# STM32H7_POWER_MISCELLANEOUS.net
KiCad netlist of a schematic drawn in Altium Designer
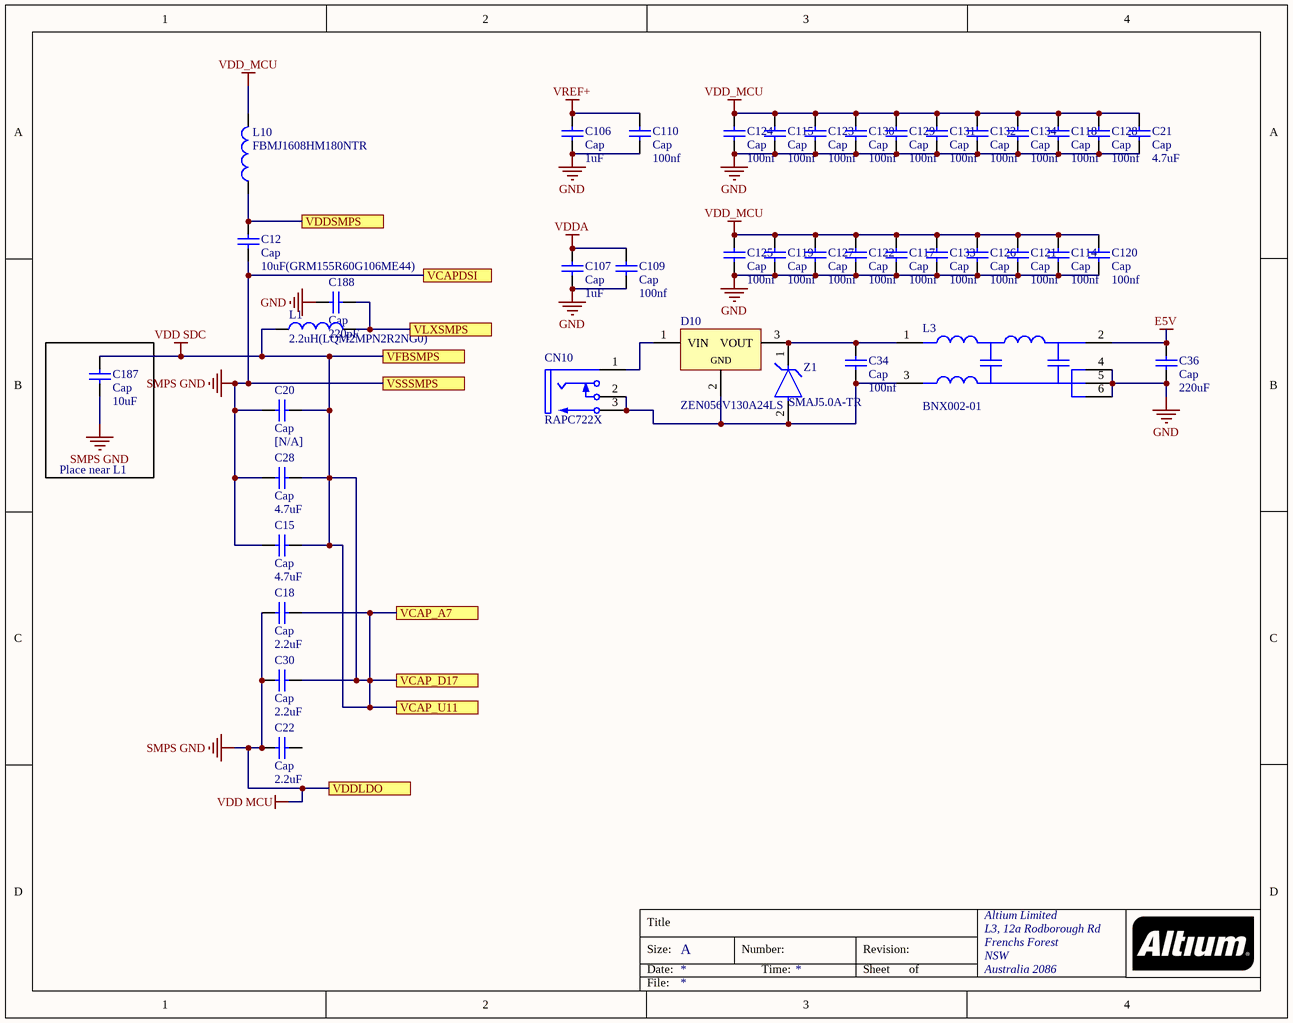
[diagram p0: STM32H7_POWER_MISCELLANEOUS.SchDoc]

(export (version "E")
  (design (tool "Eeschema 10.0.6"))
  (components
    (comp (ref "C12")
      (value "Cap")
      (footprint "RAD-0.3")
      (description "Capacitor")
      (fields
        (field (name "ALTIUM_VALUE") "10uF(GRM155R60G106ME44)")
        (field (name "PUBLISHER") "Altium Limited")
      )
      (libsource (lib "Miscellaneous Devices") (part "Cap"))
    )
    (comp (ref "C15")
      (value "Cap")
      (footprint "RAD-0.3")
      (description "Capacitor")
      (fields (field (name "ALTIUM_VALUE") "4.7uF") (field (name "PUBLISHER") "Altium Limited"))
      (libsource (lib "Miscellaneous Devices") (part "Cap"))
    )
    (comp (ref "C18")
      (value "Cap")
      (footprint "RAD-0.3")
      (description "Capacitor")
      (fields (field (name "ALTIUM_VALUE") "2.2uF") (field (name "PUBLISHER") "Altium Limited"))
      (libsource (lib "Miscellaneous Devices") (part "Cap"))
    )
    (comp (ref "C20")
      (value "Cap")
      (footprint "RAD-0.3")
      (description "Capacitor")
      (fields (field (name "ALTIUM_VALUE") "[N/A]") (field (name "PUBLISHER") "Altium Limited"))
      (libsource (lib "Miscellaneous Devices") (part "Cap"))
    )
    (comp (ref "C21")
      (value "Cap")
      (footprint "RAD-0.3")
      (description "Capacitor")
      (fields (field (name "ALTIUM_VALUE") "4.7uF") (field (name "PUBLISHER") "Altium Limited"))
      (libsource (lib "Miscellaneous Devices") (part "Cap"))
    )
    (comp (ref "C22")
      (value "Cap")
      (footprint "RAD-0.3")
      (description "Capacitor")
      (fields (field (name "ALTIUM_VALUE") "2.2uF") (field (name "PUBLISHER") "Altium Limited"))
      (libsource (lib "Miscellaneous Devices") (part "Cap"))
    )
    (comp (ref "C28")
      (value "Cap")
      (footprint "RAD-0.3")
      (description "Capacitor")
      (fields (field (name "ALTIUM_VALUE") "4.7uF") (field (name "PUBLISHER") "Altium Limited"))
      (libsource (lib "Miscellaneous Devices") (part "Cap"))
    )
    (comp (ref "C30")
      (value "Cap")
      (footprint "RAD-0.3")
      (description "Capacitor")
      (fields (field (name "ALTIUM_VALUE") "2.2uF") (field (name "PUBLISHER") "Altium Limited"))
      (libsource (lib "Miscellaneous Devices") (part "Cap"))
    )
    (comp (ref "C34")
      (value "Cap")
      (footprint "RAD-0.3")
      (description "Capacitor")
      (fields (field (name "ALTIUM_VALUE") "100nf") (field (name "PUBLISHER") "Altium Limited"))
      (libsource (lib "Miscellaneous Devices") (part "Cap"))
    )
    (comp (ref "C36")
      (value "Cap")
      (footprint "RAD-0.3")
      (description "Capacitor")
      (fields (field (name "ALTIUM_VALUE") "220uF") (field (name "PUBLISHER") "Altium Limited"))
      (libsource (lib "Miscellaneous Devices") (part "Cap"))
    )
    (comp (ref "C106")
      (value "Cap")
      (footprint "RAD-0.3")
      (description "Capacitor")
      (fields (field (name "ALTIUM_VALUE") "1uF") (field (name "PUBLISHER") "Altium Limited"))
      (libsource (lib "Miscellaneous Devices") (part "Cap"))
    )
    (comp (ref "C107")
      (value "Cap")
      (footprint "RAD-0.3")
      (description "Capacitor")
      (fields (field (name "ALTIUM_VALUE") "1uF") (field (name "PUBLISHER") "Altium Limited"))
      (libsource (lib "Miscellaneous Devices") (part "Cap"))
    )
    (comp (ref "C109")
      (value "Cap")
      (footprint "RAD-0.3")
      (description "Capacitor")
      (fields (field (name "ALTIUM_VALUE") "100nf") (field (name "PUBLISHER") "Altium Limited"))
      (libsource (lib "Miscellaneous Devices") (part "Cap"))
    )
    (comp (ref "C110")
      (value "Cap")
      (footprint "RAD-0.3")
      (description "Capacitor")
      (fields (field (name "ALTIUM_VALUE") "100nf") (field (name "PUBLISHER") "Altium Limited"))
      (libsource (lib "Miscellaneous Devices") (part "Cap"))
    )
    (comp (ref "C114")
      (value "Cap")
      (footprint "RAD-0.3")
      (description "Capacitor")
      (fields (field (name "ALTIUM_VALUE") "100nf") (field (name "PUBLISHER") "Altium Limited"))
      (libsource (lib "Miscellaneous Devices") (part "Cap"))
    )
    (comp (ref "C115")
      (value "Cap")
      (footprint "RAD-0.3")
      (description "Capacitor")
      (fields (field (name "ALTIUM_VALUE") "100nf") (field (name "PUBLISHER") "Altium Limited"))
      (libsource (lib "Miscellaneous Devices") (part "Cap"))
    )
    (comp (ref "C117")
      (value "Cap")
      (footprint "RAD-0.3")
      (description "Capacitor")
      (fields (field (name "ALTIUM_VALUE") "100nf") (field (name "PUBLISHER") "Altium Limited"))
      (libsource (lib "Miscellaneous Devices") (part "Cap"))
    )
    (comp (ref "C118")
      (value "Cap")
      (footprint "RAD-0.3")
      (description "Capacitor")
      (fields (field (name "ALTIUM_VALUE") "100nf") (field (name "PUBLISHER") "Altium Limited"))
      (libsource (lib "Miscellaneous Devices") (part "Cap"))
    )
    (comp (ref "C119")
      (value "Cap")
      (footprint "RAD-0.3")
      (description "Capacitor")
      (fields (field (name "ALTIUM_VALUE") "100nf") (field (name "PUBLISHER") "Altium Limited"))
      (libsource (lib "Miscellaneous Devices") (part "Cap"))
    )
    (comp (ref "C120")
      (value "Cap")
      (footprint "RAD-0.3")
      (description "Capacitor")
      (fields (field (name "ALTIUM_VALUE") "100nf") (field (name "PUBLISHER") "Altium Limited"))
      (libsource (lib "Miscellaneous Devices") (part "Cap"))
    )
    (comp (ref "C121")
      (value "Cap")
      (footprint "RAD-0.3")
      (description "Capacitor")
      (fields (field (name "ALTIUM_VALUE") "100nf") (field (name "PUBLISHER") "Altium Limited"))
      (libsource (lib "Miscellaneous Devices") (part "Cap"))
    )
    (comp (ref "C122")
      (value "Cap")
      (footprint "RAD-0.3")
      (description "Capacitor")
      (fields (field (name "ALTIUM_VALUE") "100nf") (field (name "PUBLISHER") "Altium Limited"))
      (libsource (lib "Miscellaneous Devices") (part "Cap"))
    )
    (comp (ref "C123")
      (value "Cap")
      (footprint "RAD-0.3")
      (description "Capacitor")
      (fields (field (name "ALTIUM_VALUE") "100nf") (field (name "PUBLISHER") "Altium Limited"))
      (libsource (lib "Miscellaneous Devices") (part "Cap"))
    )
    (comp (ref "C124")
      (value "Cap")
      (footprint "RAD-0.3")
      (description "Capacitor")
      (fields (field (name "ALTIUM_VALUE") "100nf") (field (name "PUBLISHER") "Altium Limited"))
      (libsource (lib "Miscellaneous Devices") (part "Cap"))
    )
    (comp (ref "C125")
      (value "Cap")
      (footprint "RAD-0.3")
      (description "Capacitor")
      (fields (field (name "ALTIUM_VALUE") "100nf") (field (name "PUBLISHER") "Altium Limited"))
      (libsource (lib "Miscellaneous Devices") (part "Cap"))
    )
    (comp (ref "C126")
      (value "Cap")
      (footprint "RAD-0.3")
      (description "Capacitor")
      (fields (field (name "ALTIUM_VALUE") "100nf") (field (name "PUBLISHER") "Altium Limited"))
      (libsource (lib "Miscellaneous Devices") (part "Cap"))
    )
    (comp (ref "C127")
      (value "Cap")
      (footprint "RAD-0.3")
      (description "Capacitor")
      (fields (field (name "ALTIUM_VALUE") "100nf") (field (name "PUBLISHER") "Altium Limited"))
      (libsource (lib "Miscellaneous Devices") (part "Cap"))
    )
    (comp (ref "C128")
      (value "Cap")
      (footprint "RAD-0.3")
      (description "Capacitor")
      (fields (field (name "ALTIUM_VALUE") "100nf") (field (name "PUBLISHER") "Altium Limited"))
      (libsource (lib "Miscellaneous Devices") (part "Cap"))
    )
    (comp (ref "C129")
      (value "Cap")
      (footprint "RAD-0.3")
      (description "Capacitor")
      (fields (field (name "ALTIUM_VALUE") "100nf") (field (name "PUBLISHER") "Altium Limited"))
      (libsource (lib "Miscellaneous Devices") (part "Cap"))
    )
    (comp (ref "C130")
      (value "Cap")
      (footprint "RAD-0.3")
      (description "Capacitor")
      (fields (field (name "ALTIUM_VALUE") "100nf") (field (name "PUBLISHER") "Altium Limited"))
      (libsource (lib "Miscellaneous Devices") (part "Cap"))
    )
    (comp (ref "C131")
      (value "Cap")
      (footprint "RAD-0.3")
      (description "Capacitor")
      (fields (field (name "ALTIUM_VALUE") "100nf") (field (name "PUBLISHER") "Altium Limited"))
      (libsource (lib "Miscellaneous Devices") (part "Cap"))
    )
    (comp (ref "C132")
      (value "Cap")
      (footprint "RAD-0.3")
      (description "Capacitor")
      (fields (field (name "ALTIUM_VALUE") "100nf") (field (name "PUBLISHER") "Altium Limited"))
      (libsource (lib "Miscellaneous Devices") (part "Cap"))
    )
    (comp (ref "C133")
      (value "Cap")
      (footprint "RAD-0.3")
      (description "Capacitor")
      (fields (field (name "ALTIUM_VALUE") "100nf") (field (name "PUBLISHER") "Altium Limited"))
      (libsource (lib "Miscellaneous Devices") (part "Cap"))
    )
    (comp (ref "C134")
      (value "Cap")
      (footprint "RAD-0.3")
      (description "Capacitor")
      (fields (field (name "ALTIUM_VALUE") "100nf") (field (name "PUBLISHER") "Altium Limited"))
      (libsource (lib "Miscellaneous Devices") (part "Cap"))
    )
    (comp (ref "C187")
      (value "Cap")
      (footprint "RAD-0.3")
      (description "Capacitor")
      (fields (field (name "ALTIUM_VALUE") "10uF") (field (name "PUBLISHER") "Altium Limited"))
      (libsource (lib "Miscellaneous Devices") (part "Cap"))
    )
    (comp (ref "C188")
      (value "Cap")
      (footprint "RAD-0.3")
      (description "Capacitor")
      (fields (field (name "ALTIUM_VALUE") "220pF") (field (name "PUBLISHER") "Altium Limited"))
      (libsource (lib "Miscellaneous Devices") (part "Cap"))
    )
    (comp (ref "CN10")
      (value "RAPC722X")
      (footprint "SWITCH-RAPC712X-3_V")
      (description "Power Jack, 5 A, 3-Pin THD, RoHS, Bulk")
      (fields (field (name "MANUFACTURER") "Switchcraft"))
      (libsource (lib "Altium Content Vault") (part "SWITCH-RAPC712X-3"))
    )
    (comp (ref "D10")
      (value "ZEN056V130A24LS")
      (footprint "TECO-ZEN056V130A24LS_V")
      (fields (field (name "MANUFACTURER") "TE Connectivity"))
      (libsource (lib "Altium Content Vault") (part "TECO-ZEN056V130A24LS-3"))
    )
    (comp (ref "L1")
      (value "2.2uH(LQM2MPN2R2NG0)")
      (footprint "0402-A")
      (fields (field (name "PUBLISHER") "Altium Limited"))
      (libsource (lib "Miscellaneous Devices") (part "Inductor"))
    )
    (comp (ref "L3")
      (value "BNX002-01")
      (footprint "MURA-BNX002-6")
      (description "MURATA BNX002-01 FILTER, POWER, EMI, 10A")
      (fields (field (name "MANUFACTURER") "Murata"))
      (libsource (lib "Altium Content Vault") (part "MURA-BNX002-6"))
    )
    (comp (ref "L10")
      (value "FBMJ1608HM180NTR")
      (footprint "0402-A")
      (fields (field (name "PUBLISHER") "Altium Limited"))
      (libsource (lib "Miscellaneous Devices") (part "Inductor"))
    )
    (comp (ref "Z1")
      (value "SMAJ5.0A-TR")
      (footprint "FP-SMA-MFG")
      (description "13.4V Clamp 174A (8/20µs) Ipp Tvs Diode Surface Mount SMA (DO-214AC)")
      (fields (field (name "MANUFACTURER") "STMicroelectronics"))
      (libsource (lib "Altium Content Vault") (part "7ddec9f632b8482e96f7745d0fbdf39"))
    )
  )
  (nets
    (net (code "1") (name "/VDDSMPS") (class "Default")
      (node (ref "C12") (pin "2") (pinfunction "2_2") (pintype "passive"))
      (node (ref "L10") (pin "1") (pinfunction "1_1") (pintype "passive"))
    )
    (net (code "2") (name "/VLXSMPS") (class "Default")
      (node (ref "C188") (pin "2") (pinfunction "2_2") (pintype "passive"))
      (node (ref "L1") (pin "2") (pinfunction "2_2") (pintype "passive"))
    )
    (net (code "3") (name "E5V") (class "Default")
      (node (ref "C36") (pin "2") (pinfunction "2_2") (pintype "passive"))
      (node (ref "L3") (pin "2") (pinfunction "CB_2") (pintype "power_in"))
    )
    (net (code "4") (name "GND") (class "Default")
      (node (ref "C106") (pin "1") (pinfunction "1_1") (pintype "passive"))
      (node (ref "C107") (pin "1") (pinfunction "1_1") (pintype "passive"))
      (node (ref "C109") (pin "1") (pinfunction "1_1") (pintype "passive"))
      (node (ref "C110") (pin "1") (pinfunction "1_1") (pintype "passive"))
      (node (ref "C114") (pin "1") (pinfunction "1_1") (pintype "passive"))
      (node (ref "C115") (pin "1") (pinfunction "1_1") (pintype "passive"))
      (node (ref "C117") (pin "1") (pinfunction "1_1") (pintype "passive"))
      (node (ref "C118") (pin "1") (pinfunction "1_1") (pintype "passive"))
      (node (ref "C119") (pin "1") (pinfunction "1_1") (pintype "passive"))
      (node (ref "C120") (pin "1") (pinfunction "1_1") (pintype "passive"))
      (node (ref "C121") (pin "1") (pinfunction "1_1") (pintype "passive"))
      (node (ref "C122") (pin "1") (pinfunction "1_1") (pintype "passive"))
      (node (ref "C123") (pin "1") (pinfunction "1_1") (pintype "passive"))
      (node (ref "C124") (pin "1") (pinfunction "1_1") (pintype "passive"))
      (node (ref "C125") (pin "1") (pinfunction "1_1") (pintype "passive"))
      (node (ref "C126") (pin "1") (pinfunction "1_1") (pintype "passive"))
      (node (ref "C127") (pin "1") (pinfunction "1_1") (pintype "passive"))
      (node (ref "C128") (pin "1") (pinfunction "1_1") (pintype "passive"))
      (node (ref "C129") (pin "1") (pinfunction "1_1") (pintype "passive"))
      (node (ref "C130") (pin "1") (pinfunction "1_1") (pintype "passive"))
      (node (ref "C131") (pin "1") (pinfunction "1_1") (pintype "passive"))
      (node (ref "C132") (pin "1") (pinfunction "1_1") (pintype "passive"))
      (node (ref "C133") (pin "1") (pinfunction "1_1") (pintype "passive"))
      (node (ref "C134") (pin "1") (pinfunction "1_1") (pintype "passive"))
      (node (ref "C188") (pin "1") (pinfunction "1_1") (pintype "passive"))
      (node (ref "C21") (pin "1") (pinfunction "1_1") (pintype "passive"))
      (node (ref "C36") (pin "1") (pinfunction "1_1") (pintype "passive"))
      (node (ref "L3") (pin "4") (pinfunction "CG_4") (pintype "power_in"))
      (node (ref "L3") (pin "5") (pinfunction "CG_5") (pintype "power_in"))
      (node (ref "L3") (pin "6") (pinfunction "CG_6") (pintype "power_in"))
    )
    (net (code "5") (name "Net-(D10-GND)") (class "Default")
      (node (ref "C34") (pin "1") (pinfunction "1_1") (pintype "passive"))
      (node (ref "CN10") (pin "2") (pinfunction "2_2") (pintype "passive"))
      (node (ref "CN10") (pin "3") (pinfunction "3_3") (pintype "passive"))
      (node (ref "D10") (pin "2") (pinfunction "GND_2") (pintype "passive"))
      (node (ref "L3") (pin "3") (pinfunction "PSG_3") (pintype "power_in"))
      (node (ref "Z1") (pin "2") (pinfunction "A_2") (pintype "passive"))
    )
    (net (code "6") (name "Net-(D10-VIN)") (class "Default")
      (node (ref "CN10") (pin "1") (pinfunction "1_1") (pintype "passive"))
      (node (ref "D10") (pin "1") (pinfunction "VIN_1") (pintype "passive"))
    )
    (net (code "7") (name "Net-(D10-VOUT)") (class "Default")
      (node (ref "C34") (pin "2") (pinfunction "2_2") (pintype "passive"))
      (node (ref "D10") (pin "3") (pinfunction "VOUT_3") (pintype "passive"))
      (node (ref "L3") (pin "1") (pinfunction "B_1") (pintype "power_in"))
      (node (ref "Z1") (pin "1") (pinfunction "K_1") (pintype "passive"))
    )
    (net (code "8") (name "SMPS GND") (class "Default")
      (node (ref "C12") (pin "1") (pinfunction "1_1") (pintype "passive"))
      (node (ref "C15") (pin "1") (pinfunction "1_1") (pintype "passive"))
      (node (ref "C18") (pin "1") (pinfunction "1_1") (pintype "passive"))
      (node (ref "C187") (pin "1") (pinfunction "1_1") (pintype "passive"))
      (node (ref "C20") (pin "1") (pinfunction "1_1") (pintype "passive"))
      (node (ref "C22") (pin "1") (pinfunction "1_1") (pintype "passive"))
      (node (ref "C28") (pin "1") (pinfunction "1_1") (pintype "passive"))
      (node (ref "C30") (pin "1") (pinfunction "1_1") (pintype "passive"))
    )
    (net (code "9") (name "VDD SDC") (class "Default")
      (node (ref "C15") (pin "2") (pinfunction "2_2") (pintype "passive"))
      (node (ref "C18") (pin "2") (pinfunction "2_2") (pintype "passive"))
      (node (ref "C187") (pin "2") (pinfunction "2_2") (pintype "passive"))
      (node (ref "C20") (pin "2") (pinfunction "2_2") (pintype "passive"))
      (node (ref "C28") (pin "2") (pinfunction "2_2") (pintype "passive"))
      (node (ref "C30") (pin "2") (pinfunction "2_2") (pintype "passive"))
      (node (ref "L1") (pin "1") (pinfunction "1_1") (pintype "passive"))
    )
    (net (code "10") (name "VDDA") (class "Default")
      (node (ref "C107") (pin "2") (pinfunction "2_2") (pintype "passive"))
      (node (ref "C109") (pin "2") (pinfunction "2_2") (pintype "passive"))
    )
    (net (code "11") (name "VDD_MCU") (class "Default")
      (node (ref "C114") (pin "2") (pinfunction "2_2") (pintype "passive"))
      (node (ref "C115") (pin "2") (pinfunction "2_2") (pintype "passive"))
      (node (ref "C117") (pin "2") (pinfunction "2_2") (pintype "passive"))
      (node (ref "C118") (pin "2") (pinfunction "2_2") (pintype "passive"))
      (node (ref "C119") (pin "2") (pinfunction "2_2") (pintype "passive"))
      (node (ref "C120") (pin "2") (pinfunction "2_2") (pintype "passive"))
      (node (ref "C121") (pin "2") (pinfunction "2_2") (pintype "passive"))
      (node (ref "C122") (pin "2") (pinfunction "2_2") (pintype "passive"))
      (node (ref "C123") (pin "2") (pinfunction "2_2") (pintype "passive"))
      (node (ref "C124") (pin "2") (pinfunction "2_2") (pintype "passive"))
      (node (ref "C125") (pin "2") (pinfunction "2_2") (pintype "passive"))
      (node (ref "C126") (pin "2") (pinfunction "2_2") (pintype "passive"))
      (node (ref "C127") (pin "2") (pinfunction "2_2") (pintype "passive"))
      (node (ref "C128") (pin "2") (pinfunction "2_2") (pintype "passive"))
      (node (ref "C129") (pin "2") (pinfunction "2_2") (pintype "passive"))
      (node (ref "C130") (pin "2") (pinfunction "2_2") (pintype "passive"))
      (node (ref "C131") (pin "2") (pinfunction "2_2") (pintype "passive"))
      (node (ref "C132") (pin "2") (pinfunction "2_2") (pintype "passive"))
      (node (ref "C133") (pin "2") (pinfunction "2_2") (pintype "passive"))
      (node (ref "C134") (pin "2") (pinfunction "2_2") (pintype "passive"))
      (node (ref "C21") (pin "2") (pinfunction "2_2") (pintype "passive"))
      (node (ref "L10") (pin "2") (pinfunction "2_2") (pintype "passive"))
    )
    (net (code "12") (name "VREF+") (class "Default")
      (node (ref "C106") (pin "2") (pinfunction "2_2") (pintype "passive"))
      (node (ref "C110") (pin "2") (pinfunction "2_2") (pintype "passive"))
    )
    (net (code "13") (name "unconnected-(C22-Pad2)") (class "Default")
      (node (ref "C22") (pin "2") (pinfunction "2_2") (pintype "passive"))
    )
  )
)
